# Pico_board.net
KiCad netlist of a schematic drawn in EAGLE
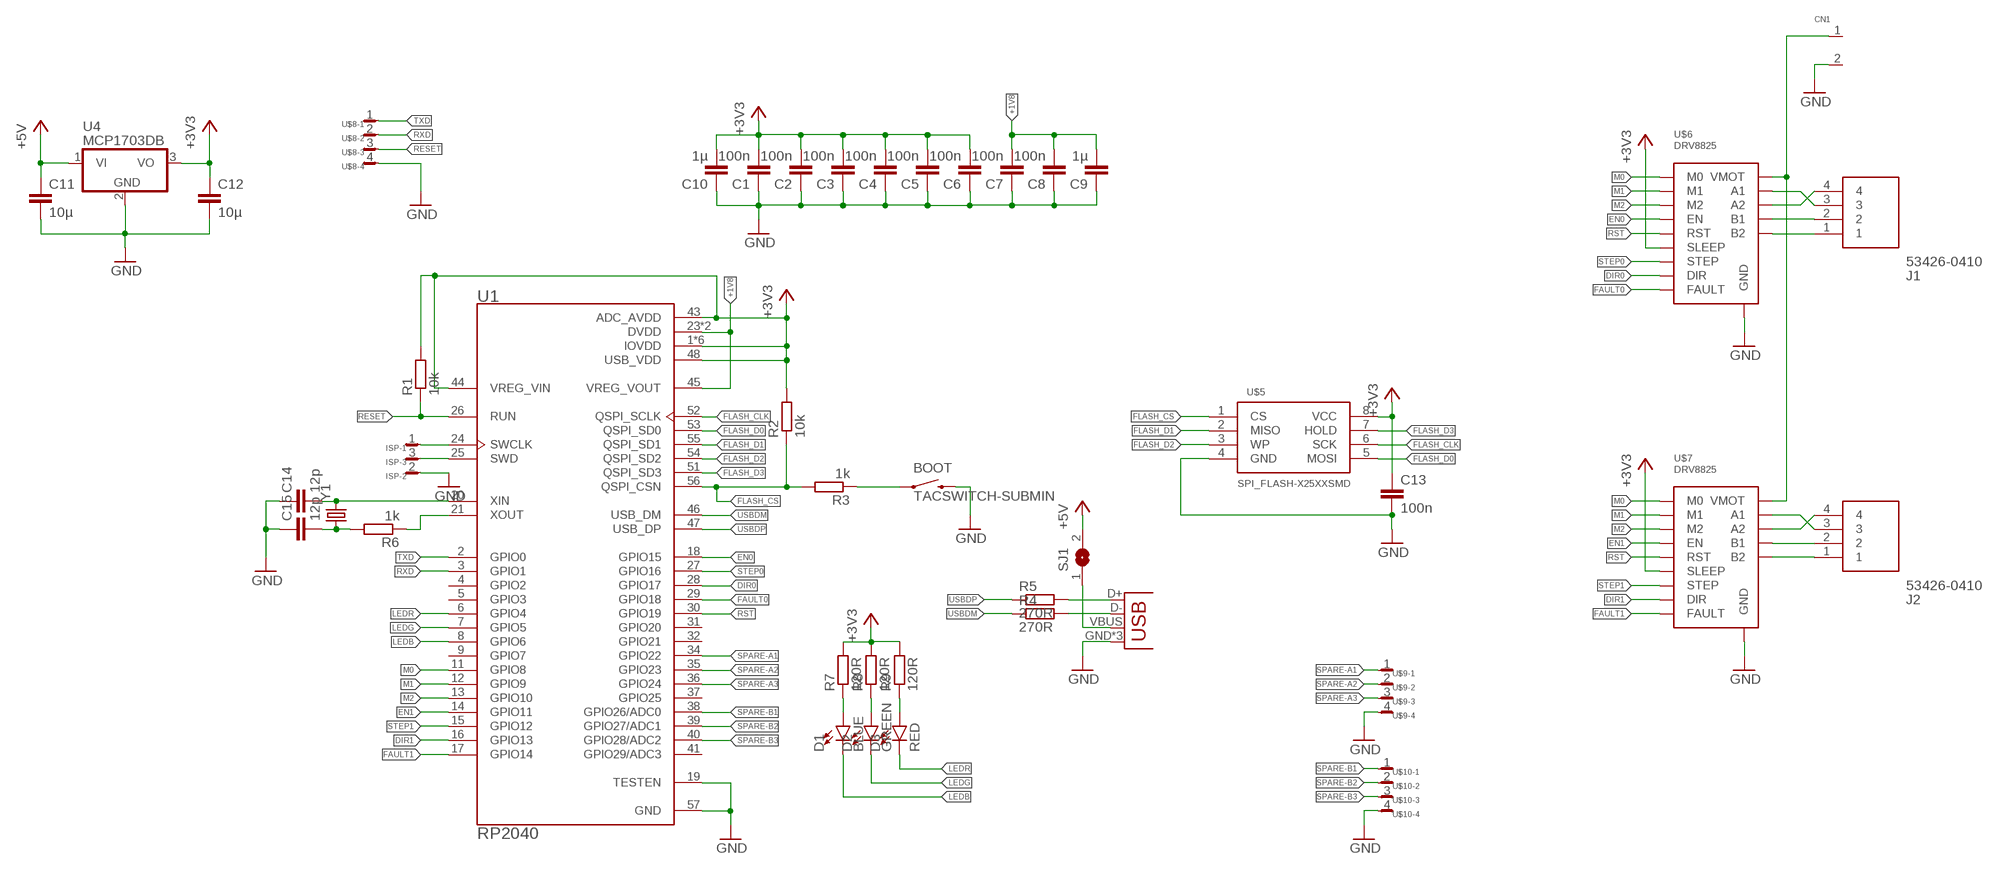
[diagram p0: schematic, sheet 1]

(export (version "E")
  (design (tool "Eeschema 10.0.6"))
  (components
    (comp (ref "BOOT")
      (value "TACSWITCH-SUBMIN")
      (footprint "eagle-import:TACSWITCH_SUBMIN")
      (libsource (lib "eagle-import") (part "TACSWITCH-SUBMIN"))
    )
    (comp (ref "C1")
      (value "100n")
      (footprint "eagle-import:C0402K")
      (libsource (lib "eagle-import") (part "C-EUC0402K"))
    )
    (comp (ref "C2")
      (value "100n")
      (footprint "eagle-import:C0402K")
      (libsource (lib "eagle-import") (part "C-EUC0402K"))
    )
    (comp (ref "C3")
      (value "100n")
      (footprint "eagle-import:C0402K")
      (libsource (lib "eagle-import") (part "C-EUC0402K"))
    )
    (comp (ref "C4")
      (value "100n")
      (footprint "eagle-import:C0402K")
      (libsource (lib "eagle-import") (part "C-EUC0402K"))
    )
    (comp (ref "C5")
      (value "100n")
      (footprint "eagle-import:C0402K")
      (libsource (lib "eagle-import") (part "C-EUC0402K"))
    )
    (comp (ref "C6")
      (value "100n")
      (footprint "eagle-import:C0402K")
      (libsource (lib "eagle-import") (part "C-EUC0402K"))
    )
    (comp (ref "C7")
      (value "100n")
      (footprint "eagle-import:C0402K")
      (libsource (lib "eagle-import") (part "C-EUC0402K"))
    )
    (comp (ref "C8")
      (value "100n")
      (footprint "eagle-import:C0402K")
      (libsource (lib "eagle-import") (part "C-EUC0402K"))
    )
    (comp (ref "C9")
      (value "1µ")
      (footprint "eagle-import:C0603K")
      (libsource (lib "eagle-import") (part "C-EUC0603K"))
    )
    (comp (ref "C10")
      (value "1µ")
      (footprint "eagle-import:C0603K")
      (libsource (lib "eagle-import") (part "C-EUC0603K"))
    )
    (comp (ref "C11")
      (value "10µ")
      (footprint "eagle-import:C1206K")
      (libsource (lib "eagle-import") (part "C-EUC1206K"))
    )
    (comp (ref "C12")
      (value "10µ")
      (footprint "eagle-import:C1206K")
      (libsource (lib "eagle-import") (part "C-EUC1206K"))
    )
    (comp (ref "C13")
      (value "100n")
      (footprint "eagle-import:C0402K")
      (libsource (lib "eagle-import") (part "C-EUC0402K"))
    )
    (comp (ref "C14")
      (value "12p")
      (footprint "eagle-import:C0402K")
      (libsource (lib "eagle-import") (part "C-EUC0402K"))
    )
    (comp (ref "C15")
      (value "12p")
      (footprint "eagle-import:C0402K")
      (libsource (lib "eagle-import") (part "C-EUC0402K"))
    )
    (comp (ref "CN1")
      (value "2PIN_SCREW_TRM")
      (footprint "eagle-import:CONN2P")
      (libsource (lib "eagle-import") (part "2PIN_SCREW_TRM"))
    )
    (comp (ref "D1")
      (value "BLUE")
      (footprint "eagle-import:LED-0603")
      (libsource (lib "eagle-import") (part "LED-BLUE0603"))
    )
    (comp (ref "D2")
      (value "GREEN")
      (footprint "eagle-import:LED-0603")
      (libsource (lib "eagle-import") (part "LED-GREEN0603"))
    )
    (comp (ref "D3")
      (value "RED")
      (footprint "eagle-import:LED-0603")
      (libsource (lib "eagle-import") (part "LED-RED0603"))
    )
    (comp (ref "ISP")
      (value "SM03B-SRSS-TB")
      (footprint "eagle-import:SM03B-SRSS-TB")
      (libsource (lib "eagle-import") (part "SM03B-SRSS-TB"))
    )
    (comp (ref "J1")
      (value "53426-0410")
      (footprint "eagle-import:SHDRRA4W55P0X250_1X4_1240X1150")
      (fields (field (name "MOUSER_PART_NUMBER") "538-53426-0410"))
      (libsource (lib "eagle-import") (part "53426-0410"))
    )
    (comp (ref "J2")
      (value "53426-0410")
      (footprint "eagle-import:SHDRRA4W55P0X250_1X4_1240X1150")
      (fields (field (name "MOUSER_PART_NUMBER") "538-53426-0410"))
      (libsource (lib "eagle-import") (part "53426-0410"))
    )
    (comp (ref "JP1")
      (value "USB-MICROB")
      (footprint "eagle-import:USB-MICROB")
      (libsource (lib "eagle-import") (part "USB-MICROB"))
    )
    (comp (ref "R1")
      (value "10k")
      (footprint "eagle-import:R0402")
      (libsource (lib "eagle-import") (part "R-EU_R0402-"))
    )
    (comp (ref "R2")
      (value "10k")
      (footprint "eagle-import:R0402")
      (libsource (lib "eagle-import") (part "R-EU_R0402-"))
    )
    (comp (ref "R3")
      (value "1k")
      (footprint "eagle-import:R0402")
      (libsource (lib "eagle-import") (part "R-EU_R0402-"))
    )
    (comp (ref "R4")
      (value "270R")
      (footprint "eagle-import:R0402")
      (libsource (lib "eagle-import") (part "R-EU_R0402-"))
    )
    (comp (ref "R5")
      (value "270R")
      (footprint "eagle-import:R0402")
      (libsource (lib "eagle-import") (part "R-EU_R0402-"))
    )
    (comp (ref "R6")
      (value "1k")
      (footprint "eagle-import:R0402")
      (libsource (lib "eagle-import") (part "R-EU_R0402-"))
    )
    (comp (ref "R7")
      (value "120R")
      (footprint "eagle-import:R0402")
      (libsource (lib "eagle-import") (part "R-EU_R0402-"))
    )
    (comp (ref "R8")
      (value "120R")
      (footprint "eagle-import:R0402")
      (libsource (lib "eagle-import") (part "R-EU_R0402-"))
    )
    (comp (ref "R9")
      (value "120R")
      (footprint "eagle-import:R0402")
      (libsource (lib "eagle-import") (part "R-EU_R0402-"))
    )
    (comp (ref "SJ1") (value "SJ") (footprint "eagle-import:SJ") (libsource (lib "eagle-import") (part "SJ")))
    (comp (ref "U$5")
      (value "SPI_FLASH-X25XXSMD")
      (footprint "eagle-import:SO08")
      (libsource (lib "eagle-import") (part "SPI_FLASH-X25XXSMD"))
    )
    (comp (ref "U$6")
      (value "DRV8825")
      (footprint "eagle-import:POLOLU")
      (libsource (lib "eagle-import") (part "POLOLU"))
    )
    (comp (ref "U$7")
      (value "DRV8825")
      (footprint "eagle-import:POLOLU")
      (libsource (lib "eagle-import") (part "POLOLU"))
    )
    (comp (ref "U$8")
      (value "SM04B-SRSS-TB")
      (footprint "eagle-import:SM04B-SRSS-TB")
      (libsource (lib "eagle-import") (part "SM04B-SRSS-TB"))
    )
    (comp (ref "U$9")
      (value "SM04B-SRSS-TB")
      (footprint "eagle-import:SM04B-SRSS-TB")
      (libsource (lib "eagle-import") (part "SM04B-SRSS-TB"))
    )
    (comp (ref "U$10")
      (value "SM04B-SRSS-TB")
      (footprint "eagle-import:SM04B-SRSS-TB")
      (libsource (lib "eagle-import") (part "SM04B-SRSS-TB"))
    )
    (comp (ref "U1")
      (value "RP2040")
      (footprint "eagle-import:QFN40P700X700X90-57N")
      (fields (field (name "MF") "Raspberry Pi"))
      (libsource (lib "eagle-import") (part "RP2040"))
    )
    (comp (ref "U4")
      (value "MCP1703DB")
      (footprint "eagle-import:SOT223")
      (libsource (lib "eagle-import") (part "MCP1703DB"))
    )
    (comp (ref "Y1")
      (value "CRYSTAL5X3")
      (footprint "eagle-import:CRYSTAL-SMD-5X3")
      (libsource (lib "eagle-import") (part "CRYSTAL5X3"))
    )
  )
  (nets
    (net (code "1") (name "+1V8") (class "Default")
      (node (ref "C7") (pin "2") (pinfunction "2_2") (pintype "passive"))
      (node (ref "C8") (pin "2") (pinfunction "2_2") (pintype "passive"))
      (node (ref "C9") (pin "2") (pinfunction "2_2") (pintype "passive"))
      (node (ref "U1") (pin "23") (pinfunction "DVDD_23") (pintype "power_in"))
      (node (ref "U1") (pin "45") (pinfunction "VREG_VOUT_45") (pintype "output"))
      (node (ref "U1") (pin "50") (pinfunction "DVDD_50") (pintype "power_in"))
    )
    (net (code "2") (name "+3V3") (class "Default")
      (node (ref "C1") (pin "2") (pinfunction "2_2") (pintype "passive"))
      (node (ref "C10") (pin "2") (pinfunction "2_2") (pintype "passive"))
      (node (ref "C12") (pin "1") (pinfunction "1_1") (pintype "passive"))
      (node (ref "C13") (pin "1") (pinfunction "1_1") (pintype "passive"))
      (node (ref "C2") (pin "2") (pinfunction "2_2") (pintype "passive"))
      (node (ref "C3") (pin "2") (pinfunction "2_2") (pintype "passive"))
      (node (ref "C4") (pin "2") (pinfunction "2_2") (pintype "passive"))
      (node (ref "C5") (pin "2") (pinfunction "2_2") (pintype "passive"))
      (node (ref "C6") (pin "2") (pinfunction "2_2") (pintype "passive"))
      (node (ref "R1") (pin "2") (pinfunction "2_2") (pintype "passive"))
      (node (ref "R2") (pin "2") (pinfunction "2_2") (pintype "passive"))
      (node (ref "R7") (pin "2") (pinfunction "2_2") (pintype "passive"))
      (node (ref "R8") (pin "2") (pinfunction "2_2") (pintype "passive"))
      (node (ref "R9") (pin "2") (pinfunction "2_2") (pintype "passive"))
      (node (ref "U$5") (pin "8") (pinfunction "VCC_8") (pintype "bidirectional"))
      (node (ref "U$6") (pin "SLEEP") (pinfunction "SLEEP_SLEEP") (pintype "bidirectional"))
      (node (ref "U$7") (pin "SLEEP") (pinfunction "SLEEP_SLEEP") (pintype "bidirectional"))
      (node (ref "U1") (pin "1") (pinfunction "IOVDD_1") (pintype "power_in"))
      (node (ref "U1") (pin "10") (pinfunction "IOVDD_10") (pintype "power_in"))
      (node (ref "U1") (pin "22") (pinfunction "IOVDD_22") (pintype "power_in"))
      (node (ref "U1") (pin "33") (pinfunction "IOVDD_33") (pintype "power_in"))
      (node (ref "U1") (pin "42") (pinfunction "IOVDD_42") (pintype "power_in"))
      (node (ref "U1") (pin "43") (pinfunction "ADC_AVDD_43") (pintype "power_in"))
      (node (ref "U1") (pin "44") (pinfunction "VREG_VIN_44") (pintype "input"))
      (node (ref "U1") (pin "48") (pinfunction "USB_VDD_48") (pintype "power_in"))
      (node (ref "U1") (pin "49") (pinfunction "IOVDD_49") (pintype "power_in"))
      (node (ref "U4") (pin "3") (pinfunction "VO_3") (pintype "passive"))
    )
    (net (code "3") (name "+5V") (class "Default")
      (node (ref "C11") (pin "1") (pinfunction "1_1") (pintype "passive"))
      (node (ref "SJ1") (pin "2") (pinfunction "2_2") (pintype "passive"))
      (node (ref "U4") (pin "1") (pinfunction "VI_1") (pintype "input"))
    )
    (net (code "4") (name "DIR0") (class "Default")
      (node (ref "U$6") (pin "DIR") (pinfunction "DIR_DIR") (pintype "bidirectional"))
      (node (ref "U1") (pin "28") (pinfunction "GPIO17_28") (pintype "bidirectional"))
    )
    (net (code "5") (name "DIR1") (class "Default")
      (node (ref "U$7") (pin "DIR") (pinfunction "DIR_DIR") (pintype "bidirectional"))
      (node (ref "U1") (pin "16") (pinfunction "GPIO13_16") (pintype "bidirectional"))
    )
    (net (code "6") (name "EN0") (class "Default")
      (node (ref "U$6") (pin "ENABLE") (pinfunction "EN_ENABLE") (pintype "bidirectional"))
      (node (ref "U1") (pin "18") (pinfunction "GPIO15_18") (pintype "bidirectional"))
    )
    (net (code "7") (name "EN1") (class "Default")
      (node (ref "U$7") (pin "ENABLE") (pinfunction "EN_ENABLE") (pintype "bidirectional"))
      (node (ref "U1") (pin "14") (pinfunction "GPIO11_14") (pintype "bidirectional"))
    )
    (net (code "8") (name "FAULT0") (class "Default")
      (node (ref "U$6") (pin "FAULT") (pinfunction "FAULT_FAULT") (pintype "bidirectional"))
      (node (ref "U1") (pin "29") (pinfunction "GPIO18_29") (pintype "bidirectional"))
    )
    (net (code "9") (name "FAULT1") (class "Default")
      (node (ref "U$7") (pin "FAULT") (pinfunction "FAULT_FAULT") (pintype "bidirectional"))
      (node (ref "U1") (pin "17") (pinfunction "GPIO14_17") (pintype "bidirectional"))
    )
    (net (code "10") (name "FLASH_CLK") (class "Default")
      (node (ref "U$5") (pin "6") (pinfunction "SCK_6") (pintype "bidirectional"))
      (node (ref "U1") (pin "52") (pinfunction "QSPI_SCLK_52") (pintype "bidirectional"))
    )
    (net (code "11") (name "FLASH_CS") (class "Default")
      (node (ref "R2") (pin "1") (pinfunction "1_1") (pintype "passive"))
      (node (ref "R3") (pin "2") (pinfunction "2_2") (pintype "passive"))
      (node (ref "U$5") (pin "1") (pinfunction "CS_1") (pintype "bidirectional"))
      (node (ref "U1") (pin "56") (pinfunction "QSPI_CSN_56") (pintype "bidirectional"))
    )
    (net (code "12") (name "FLASH_D0") (class "Default")
      (node (ref "U$5") (pin "5") (pinfunction "MOSI_5") (pintype "bidirectional"))
      (node (ref "U1") (pin "53") (pinfunction "QSPI_SD0_53") (pintype "bidirectional"))
    )
    (net (code "13") (name "FLASH_D1") (class "Default")
      (node (ref "U$5") (pin "2") (pinfunction "MISO_2") (pintype "bidirectional"))
      (node (ref "U1") (pin "55") (pinfunction "QSPI_SD1_55") (pintype "bidirectional"))
    )
    (net (code "14") (name "FLASH_D2") (class "Default")
      (node (ref "U$5") (pin "3") (pinfunction "WP_3") (pintype "bidirectional"))
      (node (ref "U1") (pin "54") (pinfunction "QSPI_SD2_54") (pintype "bidirectional"))
    )
    (net (code "15") (name "FLASH_D3") (class "Default")
      (node (ref "U$5") (pin "7") (pinfunction "HOLD_7") (pintype "bidirectional"))
      (node (ref "U1") (pin "51") (pinfunction "QSPI_SD3_51") (pintype "bidirectional"))
    )
    (net (code "16") (name "GND") (class "Default")
      (node (ref "BOOT") (pin "-2") (pinfunction "2_-2") (pintype "passive"))
      (node (ref "C1") (pin "1") (pinfunction "1_1") (pintype "passive"))
      (node (ref "C10") (pin "1") (pinfunction "1_1") (pintype "passive"))
      (node (ref "C11") (pin "2") (pinfunction "2_2") (pintype "passive"))
      (node (ref "C12") (pin "2") (pinfunction "2_2") (pintype "passive"))
      (node (ref "C13") (pin "2") (pinfunction "2_2") (pintype "passive"))
      (node (ref "C14") (pin "1") (pinfunction "1_1") (pintype "passive"))
      (node (ref "C15") (pin "1") (pinfunction "1_1") (pintype "passive"))
      (node (ref "C2") (pin "1") (pinfunction "1_1") (pintype "passive"))
      (node (ref "C3") (pin "1") (pinfunction "1_1") (pintype "passive"))
      (node (ref "C4") (pin "1") (pinfunction "1_1") (pintype "passive"))
      (node (ref "C5") (pin "1") (pinfunction "1_1") (pintype "passive"))
      (node (ref "C6") (pin "1") (pinfunction "1_1") (pintype "passive"))
      (node (ref "C7") (pin "1") (pinfunction "1_1") (pintype "passive"))
      (node (ref "C8") (pin "1") (pinfunction "1_1") (pintype "passive"))
      (node (ref "C9") (pin "1") (pinfunction "1_1") (pintype "passive"))
      (node (ref "CN1") (pin "2") (pintype "bidirectional"))
      (node (ref "ISP") (pin "2") (pinfunction "P_2") (pintype "bidirectional"))
      (node (ref "JP1") (pin "GND") (pinfunction "GND_GND") (pintype "bidirectional"))
      (node (ref "JP1") (pin "MT1") (pinfunction "GND_MT1") (pintype "bidirectional"))
      (node (ref "JP1") (pin "MT2") (pinfunction "GND_MT2") (pintype "bidirectional"))
      (node (ref "U$10") (pin "4") (pinfunction "P_4") (pintype "bidirectional"))
      (node (ref "U$5") (pin "4") (pinfunction "GND_4") (pintype "bidirectional"))
      (node (ref "U$6") (pin "GND@1") (pinfunction "GND_GND@1") (pintype "bidirectional"))
      (node (ref "U$6") (pin "GND@2") (pinfunction "GND_GND@2") (pintype "bidirectional"))
      (node (ref "U$7") (pin "GND@1") (pinfunction "GND_GND@1") (pintype "bidirectional"))
      (node (ref "U$7") (pin "GND@2") (pinfunction "GND_GND@2") (pintype "bidirectional"))
      (node (ref "U$8") (pin "4") (pinfunction "P_4") (pintype "bidirectional"))
      (node (ref "U$9") (pin "4") (pinfunction "P_4") (pintype "bidirectional"))
      (node (ref "U1") (pin "19") (pinfunction "TESTEN_19") (pintype "passive"))
      (node (ref "U1") (pin "57") (pinfunction "GND_57") (pintype "power_in"))
      (node (ref "U4") (pin "2") (pinfunction "GND_2") (pintype "passive"))
    )
    (net (code "17") (name "LEDB") (class "Default")
      (node (ref "D1") (pin "C") (pinfunction "C_C") (pintype "passive"))
      (node (ref "U1") (pin "8") (pinfunction "GPIO6_8") (pintype "bidirectional"))
    )
    (net (code "18") (name "LEDG") (class "Default")
      (node (ref "D2") (pin "C") (pinfunction "C_C") (pintype "passive"))
      (node (ref "U1") (pin "7") (pinfunction "GPIO5_7") (pintype "bidirectional"))
    )
    (net (code "19") (name "LEDR") (class "Default")
      (node (ref "D3") (pin "C") (pinfunction "C_C") (pintype "passive"))
      (node (ref "U1") (pin "6") (pinfunction "GPIO4_6") (pintype "bidirectional"))
    )
    (net (code "20") (name "M0") (class "Default")
      (node (ref "U$6") (pin "M0") (pinfunction "M0_M0") (pintype "bidirectional"))
      (node (ref "U$7") (pin "M0") (pinfunction "M0_M0") (pintype "bidirectional"))
      (node (ref "U1") (pin "11") (pinfunction "GPIO8_11") (pintype "bidirectional"))
    )
    (net (code "21") (name "M1") (class "Default")
      (node (ref "U$6") (pin "M1") (pinfunction "M1_M1") (pintype "bidirectional"))
      (node (ref "U$7") (pin "M1") (pinfunction "M1_M1") (pintype "bidirectional"))
      (node (ref "U1") (pin "12") (pinfunction "GPIO9_12") (pintype "bidirectional"))
    )
    (net (code "22") (name "M2") (class "Default")
      (node (ref "U$6") (pin "M2") (pinfunction "M2_M2") (pintype "bidirectional"))
      (node (ref "U$7") (pin "M2") (pinfunction "M2_M2") (pintype "bidirectional"))
      (node (ref "U1") (pin "13") (pinfunction "GPIO10_13") (pintype "bidirectional"))
    )
    (net (code "23") (name "Net-(BOOT-1)") (class "Default")
      (node (ref "BOOT") (pin "-1") (pinfunction "1_-1") (pintype "passive"))
      (node (ref "R3") (pin "1") (pinfunction "1_1") (pintype "passive"))
    )
    (net (code "24") (name "Net-(C15-Pad2)") (class "Default")
      (node (ref "C15") (pin "2") (pinfunction "2_2") (pintype "passive"))
      (node (ref "R6") (pin "2") (pinfunction "2_2") (pintype "passive"))
      (node (ref "Y1") (pin "1") (pinfunction "1_1") (pintype "passive"))
    )
    (net (code "25") (name "Net-(CN1-Pad1)") (class "Default")
      (node (ref "CN1") (pin "1") (pintype "bidirectional"))
      (node (ref "U$6") (pin "VMOT") (pinfunction "VMOT_VMOT") (pintype "bidirectional"))
      (node (ref "U$7") (pin "VMOT") (pinfunction "VMOT_VMOT") (pintype "bidirectional"))
    )
    (net (code "26") (name "Net-(D1-PadA)") (class "Default")
      (node (ref "D1") (pin "A") (pinfunction "A_A") (pintype "passive"))
      (node (ref "R7") (pin "1") (pinfunction "1_1") (pintype "passive"))
    )
    (net (code "27") (name "Net-(D2-PadA)") (class "Default")
      (node (ref "D2") (pin "A") (pinfunction "A_A") (pintype "passive"))
      (node (ref "R8") (pin "1") (pinfunction "1_1") (pintype "passive"))
    )
    (net (code "28") (name "Net-(D3-PadA)") (class "Default")
      (node (ref "D3") (pin "A") (pinfunction "A_A") (pintype "passive"))
      (node (ref "R9") (pin "1") (pinfunction "1_1") (pintype "passive"))
    )
    (net (code "29") (name "Net-(ISPA-P)") (class "Default")
      (node (ref "ISP") (pin "1") (pinfunction "P_1") (pintype "bidirectional"))
      (node (ref "U1") (pin "24") (pinfunction "SWCLK_24") (pintype "input"))
    )
    (net (code "30") (name "Net-(ISPC-P)") (class "Default")
      (node (ref "ISP") (pin "3") (pinfunction "P_3") (pintype "bidirectional"))
      (node (ref "U1") (pin "25") (pinfunction "SWD_25") (pintype "bidirectional"))
    )
    (net (code "31") (name "Net-(J1-Pad1)") (class "Default")
      (node (ref "J1") (pin "1") (pinfunction "1_1") (pintype "bidirectional"))
      (node (ref "U$6") (pin "B2") (pinfunction "B2_B2") (pintype "bidirectional"))
    )
    (net (code "32") (name "Net-(J1-Pad2)") (class "Default")
      (node (ref "J1") (pin "2") (pinfunction "2_2") (pintype "bidirectional"))
      (node (ref "U$6") (pin "B1") (pinfunction "B1_B1") (pintype "bidirectional"))
    )
    (net (code "33") (name "Net-(J1-Pad3)") (class "Default")
      (node (ref "J1") (pin "3") (pinfunction "3_3") (pintype "bidirectional"))
      (node (ref "U$6") (pin "A1") (pinfunction "A1_A1") (pintype "bidirectional"))
    )
    (net (code "34") (name "Net-(J1-Pad4)") (class "Default")
      (node (ref "J1") (pin "4") (pinfunction "4_4") (pintype "bidirectional"))
      (node (ref "U$6") (pin "A2") (pinfunction "A2_A2") (pintype "bidirectional"))
    )
    (net (code "35") (name "Net-(J2-Pad1)") (class "Default")
      (node (ref "J2") (pin "1") (pinfunction "1_1") (pintype "bidirectional"))
      (node (ref "U$7") (pin "B2") (pinfunction "B2_B2") (pintype "bidirectional"))
    )
    (net (code "36") (name "Net-(J2-Pad2)") (class "Default")
      (node (ref "J2") (pin "2") (pinfunction "2_2") (pintype "bidirectional"))
      (node (ref "U$7") (pin "B1") (pinfunction "B1_B1") (pintype "bidirectional"))
    )
    (net (code "37") (name "Net-(J2-Pad3)") (class "Default")
      (node (ref "J2") (pin "3") (pinfunction "3_3") (pintype "bidirectional"))
      (node (ref "U$7") (pin "A1") (pinfunction "A1_A1") (pintype "bidirectional"))
    )
    (net (code "38") (name "Net-(J2-Pad4)") (class "Default")
      (node (ref "J2") (pin "4") (pinfunction "4_4") (pintype "bidirectional"))
      (node (ref "U$7") (pin "A2") (pinfunction "A2_A2") (pintype "bidirectional"))
    )
    (net (code "39") (name "Net-(JP1-PadD+)") (class "Default")
      (node (ref "JP1") (pin "D+") (pinfunction "D+_D+") (pintype "bidirectional"))
      (node (ref "R5") (pin "2") (pinfunction "2_2") (pintype "passive"))
    )
    (net (code "40") (name "Net-(JP1-PadD-)") (class "Default")
      (node (ref "JP1") (pin "D-") (pinfunction "D-_D-") (pintype "bidirectional"))
      (node (ref "R4") (pin "2") (pinfunction "2_2") (pintype "passive"))
    )
    (net (code "41") (name "Net-(JP1-PadVBUS)") (class "Default")
      (node (ref "JP1") (pin "VBUS") (pinfunction "VBUS_VBUS") (pintype "bidirectional"))
      (node (ref "SJ1") (pin "1") (pinfunction "1_1") (pintype "passive"))
    )
    (net (code "42") (name "Net-(U1-XIN)") (class "Default")
      (node (ref "C14") (pin "2") (pinfunction "2_2") (pintype "passive"))
      (node (ref "U1") (pin "20") (pinfunction "XIN_20") (pintype "input"))
      (node (ref "Y1") (pin "3") (pinfunction "2_3") (pintype "passive"))
    )
    (net (code "43") (name "Net-(U1-XOUT)") (class "Default")
      (node (ref "R6") (pin "1") (pinfunction "1_1") (pintype "passive"))
      (node (ref "U1") (pin "21") (pinfunction "XOUT_21") (pintype "output"))
    )
    (net (code "44") (name "RESET") (class "Default")
      (node (ref "R1") (pin "1") (pinfunction "1_1") (pintype "passive"))
      (node (ref "U$8") (pin "3") (pinfunction "P_3") (pintype "bidirectional"))
      (node (ref "U1") (pin "26") (pinfunction "RUN_26") (pintype "input"))
    )
    (net (code "45") (name "RST") (class "Default")
      (node (ref "U$6") (pin "RESET") (pinfunction "RST_RESET") (pintype "bidirectional"))
      (node (ref "U$7") (pin "RESET") (pinfunction "RST_RESET") (pintype "bidirectional"))
      (node (ref "U1") (pin "30") (pinfunction "GPIO19_30") (pintype "bidirectional"))
    )
    (net (code "46") (name "RXD") (class "Default")
      (node (ref "U$8") (pin "2") (pinfunction "P_2") (pintype "bidirectional"))
      (node (ref "U1") (pin "3") (pinfunction "GPIO1_3") (pintype "bidirectional"))
    )
    (net (code "47") (name "SPARE-A1") (class "Default")
      (node (ref "U$9") (pin "1") (pinfunction "P_1") (pintype "bidirectional"))
      (node (ref "U1") (pin "34") (pinfunction "GPIO22_34") (pintype "bidirectional"))
    )
    (net (code "48") (name "SPARE-A2") (class "Default")
      (node (ref "U$9") (pin "2") (pinfunction "P_2") (pintype "bidirectional"))
      (node (ref "U1") (pin "35") (pinfunction "GPIO23_35") (pintype "bidirectional"))
    )
    (net (code "49") (name "SPARE-A3") (class "Default")
      (node (ref "U$9") (pin "3") (pinfunction "P_3") (pintype "bidirectional"))
      (node (ref "U1") (pin "36") (pinfunction "GPIO24_36") (pintype "bidirectional"))
    )
    (net (code "50") (name "SPARE-B1") (class "Default")
      (node (ref "U$10") (pin "1") (pinfunction "P_1") (pintype "bidirectional"))
      (node (ref "U1") (pin "38") (pinfunction "GPIO26/ADC0_38") (pintype "bidirectional"))
    )
    (net (code "51") (name "SPARE-B2") (class "Default")
      (node (ref "U$10") (pin "2") (pinfunction "P_2") (pintype "bidirectional"))
      (node (ref "U1") (pin "39") (pinfunction "GPIO27/ADC1_39") (pintype "bidirectional"))
    )
    (net (code "52") (name "SPARE-B3") (class "Default")
      (node (ref "U$10") (pin "3") (pinfunction "P_3") (pintype "bidirectional"))
      (node (ref "U1") (pin "40") (pinfunction "GPIO28/ADC2_40") (pintype "bidirectional"))
    )
    (net (code "53") (name "STEP0") (class "Default")
      (node (ref "U$6") (pin "STEP") (pinfunction "STEP_STEP") (pintype "bidirectional"))
      (node (ref "U1") (pin "27") (pinfunction "GPIO16_27") (pintype "bidirectional"))
    )
    (net (code "54") (name "STEP1") (class "Default")
      (node (ref "U$7") (pin "STEP") (pinfunction "STEP_STEP") (pintype "bidirectional"))
      (node (ref "U1") (pin "15") (pinfunction "GPIO12_15") (pintype "bidirectional"))
    )
    (net (code "55") (name "TXD") (class "Default")
      (node (ref "U$8") (pin "1") (pinfunction "P_1") (pintype "bidirectional"))
      (node (ref "U1") (pin "2") (pinfunction "GPIO0_2") (pintype "bidirectional"))
    )
    (net (code "56") (name "USBDM") (class "Default")
      (node (ref "R4") (pin "1") (pinfunction "1_1") (pintype "passive"))
      (node (ref "U1") (pin "46") (pinfunction "USB_DM_46") (pintype "bidirectional"))
    )
    (net (code "57") (name "USBDP") (class "Default")
      (node (ref "R5") (pin "1") (pinfunction "1_1") (pintype "passive"))
      (node (ref "U1") (pin "47") (pinfunction "USB_DP_47") (pintype "bidirectional"))
    )
    (net (code "58") (name "unconnected-(U1-GPIO2-Pad4)") (class "Default")
      (node (ref "U1") (pin "4") (pinfunction "GPIO2_4") (pintype "bidirectional"))
    )
    (net (code "59") (name "unconnected-(U1-GPIO3-Pad5)") (class "Default")
      (node (ref "U1") (pin "5") (pinfunction "GPIO3_5") (pintype "bidirectional"))
    )
    (net (code "60") (name "unconnected-(U1-GPIO7-Pad9)") (class "Default")
      (node (ref "U1") (pin "9") (pinfunction "GPIO7_9") (pintype "bidirectional"))
    )
    (net (code "61") (name "unconnected-(U1-GPIO20-Pad31)") (class "Default")
      (node (ref "U1") (pin "31") (pinfunction "GPIO20_31") (pintype "bidirectional"))
    )
    (net (code "62") (name "unconnected-(U1-GPIO21-Pad32)") (class "Default")
      (node (ref "U1") (pin "32") (pinfunction "GPIO21_32") (pintype "bidirectional"))
    )
    (net (code "63") (name "unconnected-(U1-GPIO25-Pad37)") (class "Default")
      (node (ref "U1") (pin "37") (pinfunction "GPIO25_37") (pintype "bidirectional"))
    )
    (net (code "64") (name "unconnected-(U1-GPIO29{slash}ADC3-Pad41)") (class "Default")
      (node (ref "U1") (pin "41") (pinfunction "GPIO29/ADC3_41") (pintype "bidirectional"))
    )
  )
)
